# v1.net
KiCad netlist of a schematic drawn in EAGLE
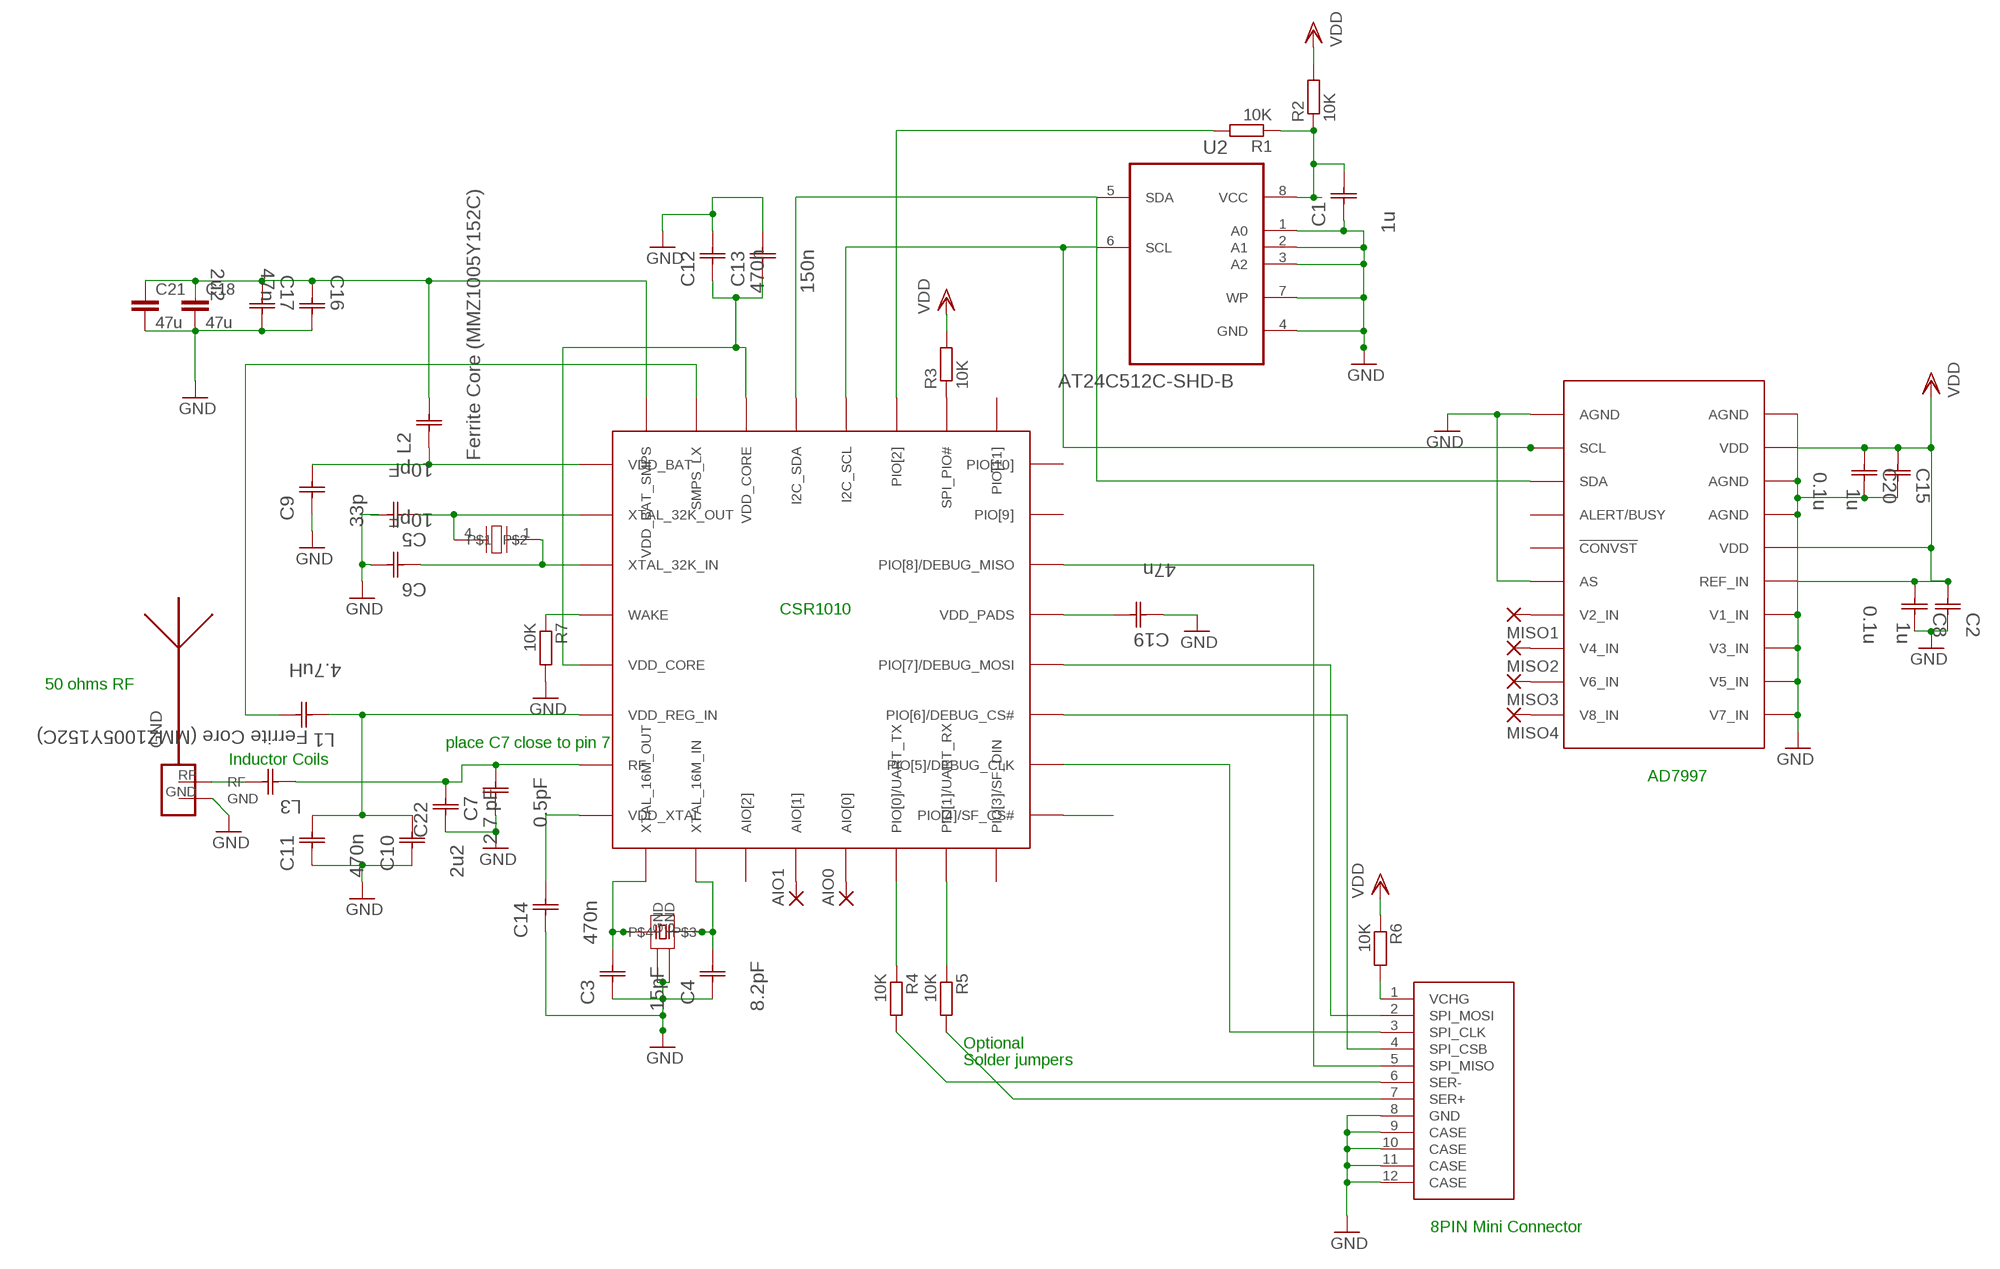
[diagram p0: schematic, sheet 1]

(export (version "E")
  (design (tool "Eeschema 10.0.6"))
  (components
    (comp (ref "AIO0")
      (value "1,6/0,8")
      (footprint "eagle-import:1,6_0,8")
      (libsource (lib "eagle-import") (part "1,6/0,8"))
    )
    (comp (ref "AIO1")
      (value "1,6/0,8")
      (footprint "eagle-import:1,6_0,8")
      (libsource (lib "eagle-import") (part "1,6/0,8"))
    )
    (comp (ref "C1")
      (value "1u")
      (footprint "eagle-import:CAPC1005X60N")
      (fields (field (name "MPN") "UQCL2A100JAT2A/500") (field (name "TOLERANCE") "±5%"))
      (libsource (lib "eagle-import") (part "UQCL2A100JAT2A/500"))
    )
    (comp (ref "C2")
      (value "1u")
      (footprint "eagle-import:CAPC1005X60N")
      (fields (field (name "MPN") "UQCL2A100JAT2A/500") (field (name "TOLERANCE") "±5%"))
      (libsource (lib "eagle-import") (part "UQCL2A100JAT2A/500"))
    )
    (comp (ref "C3")
      (value "15pF")
      (footprint "eagle-import:CAPC1005X60N")
      (fields (field (name "MPN") "UQCL2A150JAT2A/500") (field (name "TOLERANCE") "±5%"))
      (libsource (lib "eagle-import") (part "UQCL2A150JAT2A/500"))
    )
    (comp (ref "C4")
      (value "8.2pF")
      (footprint "eagle-import:CAPC1005X60N")
      (fields (field (name "MPN") "UQCL2A8R2CAT2A/500") (field (name "TOLERANCE") "±.25 pF"))
      (libsource (lib "eagle-import") (part "UQCL2A8R2CAT2A/500"))
    )
    (comp (ref "C5")
      (value "10pF")
      (footprint "eagle-import:CAPC1005X60N")
      (fields (field (name "MPN") "UQCL2A100JAT2A/500") (field (name "TOLERANCE") "±5%"))
      (libsource (lib "eagle-import") (part "UQCL2A100JAT2A/500"))
    )
    (comp (ref "C6")
      (value "10pF")
      (footprint "eagle-import:CAPC1005X60N")
      (fields (field (name "MPN") "UQCL2A100JAT2A/500") (field (name "TOLERANCE") "±5%"))
      (libsource (lib "eagle-import") (part "UQCL2A100JAT2A/500"))
    )
    (comp (ref "C7")
      (value "0.5pF")
      (footprint "eagle-import:CAPC1005X60N")
      (fields (field (name "MPN") "UQCL2A0R5BAT2A/500") (field (name "TOLERANCE") "±.1 pF"))
      (libsource (lib "eagle-import") (part "UQCL2A0R5BAT2A/500"))
    )
    (comp (ref "C8")
      (value "0.1u")
      (footprint "eagle-import:CAPC1005X60N")
      (fields (field (name "MPN") "UQCL2A100JAT2A/500") (field (name "TOLERANCE") "±5%"))
      (libsource (lib "eagle-import") (part "UQCL2A100JAT2A/500"))
    )
    (comp (ref "C9")
      (value "33p")
      (footprint "eagle-import:CAPC1005X60N")
      (fields (field (name "MPN") "UQCL2A100JAT2A/500") (field (name "TOLERANCE") "±5%"))
      (libsource (lib "eagle-import") (part "UQCL2A100JAT2A/500"))
    )
    (comp (ref "C10")
      (value "2u2")
      (footprint "eagle-import:CAPC1005X60N")
      (fields (field (name "MPN") "UQCL2A100JAT2A/500") (field (name "TOLERANCE") "±5%"))
      (libsource (lib "eagle-import") (part "UQCL2A100JAT2A/500"))
    )
    (comp (ref "C11")
      (value "470n")
      (footprint "eagle-import:CAPC1005X60N")
      (fields (field (name "MPN") "UQCL2A100JAT2A/500") (field (name "TOLERANCE") "±5%"))
      (libsource (lib "eagle-import") (part "UQCL2A100JAT2A/500"))
    )
    (comp (ref "C12")
      (value "470n")
      (footprint "eagle-import:CAPC1005X60N")
      (fields (field (name "MPN") "UQCL2A100JAT2A/500") (field (name "TOLERANCE") "±5%"))
      (libsource (lib "eagle-import") (part "UQCL2A100JAT2A/500"))
    )
    (comp (ref "C13")
      (value "150n")
      (footprint "eagle-import:CAPC1005X60N")
      (fields (field (name "MPN") "UQCL2A100JAT2A/500") (field (name "TOLERANCE") "±5%"))
      (libsource (lib "eagle-import") (part "UQCL2A100JAT2A/500"))
    )
    (comp (ref "C14")
      (value "470n")
      (footprint "eagle-import:CAPC1005X60N")
      (fields (field (name "MPN") "UQCL2A100JAT2A/500") (field (name "TOLERANCE") "±5%"))
      (libsource (lib "eagle-import") (part "UQCL2A100JAT2A/500"))
    )
    (comp (ref "C15")
      (value "1u")
      (footprint "eagle-import:CAPC1005X60N")
      (fields (field (name "MPN") "UQCL2A100JAT2A/500") (field (name "TOLERANCE") "±5%"))
      (libsource (lib "eagle-import") (part "UQCL2A100JAT2A/500"))
    )
    (comp (ref "C16")
      (value "47n")
      (footprint "eagle-import:CAPC1005X60N")
      (fields (field (name "MPN") "UQCL2A1R0BAT2A/500") (field (name "TOLERANCE") "±.1 pF"))
      (libsource (lib "eagle-import") (part "UQCL2A1R0BAT2A/500"))
    )
    (comp (ref "C17")
      (value "2u2")
      (footprint "eagle-import:CAPC1005X60N")
      (fields (field (name "MPN") "UQCL2A1R0BAT2A/500") (field (name "TOLERANCE") "±.1 pF"))
      (libsource (lib "eagle-import") (part "UQCL2A1R0BAT2A/500"))
    )
    (comp (ref "C18")
      (value "47u")
      (footprint "eagle-import:C0805")
      (libsource (lib "eagle-import") (part "C-EUC0805"))
    )
    (comp (ref "C19")
      (value "47n")
      (footprint "eagle-import:CAPC1005X60N")
      (fields (field (name "MPN") "UQCL2A100JAT2A/500") (field (name "TOLERANCE") "±5%"))
      (libsource (lib "eagle-import") (part "UQCL2A100JAT2A/500"))
    )
    (comp (ref "C20")
      (value "0.1u")
      (footprint "eagle-import:CAPC1005X60N")
      (fields (field (name "MPN") "UQCL2A100JAT2A/500") (field (name "TOLERANCE") "±5%"))
      (libsource (lib "eagle-import") (part "UQCL2A100JAT2A/500"))
    )
    (comp (ref "C21")
      (value "47u")
      (footprint "eagle-import:C0805")
      (libsource (lib "eagle-import") (part "C-EUC0805"))
    )
    (comp (ref "C22")
      (value "2.7 pF")
      (footprint "eagle-import:CAPC1005X60N")
      (fields (field (name "MPN") "UQCL2A0R5BAT2A/500") (field (name "TOLERANCE") "±.1 pF"))
      (libsource (lib "eagle-import") (part "UQCL2A0R5BAT2A/500"))
    )
    (comp (ref "GND")
      (value "ANTENNA_1LEFT")
      (footprint "eagle-import:SWRA117D_LEFT")
      (libsource (lib "eagle-import") (part "ANTENNA_1LEFT"))
    )
    (comp (ref "L1")
      (value "4.7uH")
      (footprint "eagle-import:CAPC3225X127N")
      (fields (field (name "MPN") "12107C102JAT2A") (field (name "TOLERANCE") "±5%"))
      (libsource (lib "eagle-import") (part "12107C102JAT2A"))
    )
    (comp (ref "L2")
      (value "Ferrite Core (MMZ1005Y152C)")
      (footprint "eagle-import:CAPC1005X60N")
      (fields (field (name "MPN") "UQCL2A100JAT2A/500") (field (name "TOLERANCE") "±5%"))
      (libsource (lib "eagle-import") (part "UQCL2A100JAT2A/500"))
    )
    (comp (ref "L3")
      (value "Ferrite Core (MMZ1005Y152C)")
      (footprint "eagle-import:CAPC1005X60N")
      (fields (field (name "MPN") "UQCL2A100JAT2A/500") (field (name "TOLERANCE") "±5%"))
      (libsource (lib "eagle-import") (part "UQCL2A100JAT2A/500"))
    )
    (comp (ref "MISO1")
      (value "1,6/0,8")
      (footprint "eagle-import:1,6_0,8")
      (libsource (lib "eagle-import") (part "1,6/0,8"))
    )
    (comp (ref "MISO2")
      (value "1,6/0,8")
      (footprint "eagle-import:1,6_0,8")
      (libsource (lib "eagle-import") (part "1,6/0,8"))
    )
    (comp (ref "MISO3")
      (value "1,6/0,8")
      (footprint "eagle-import:1,6_0,8")
      (libsource (lib "eagle-import") (part "1,6/0,8"))
    )
    (comp (ref "MISO4")
      (value "1,6/0,8")
      (footprint "eagle-import:1,6_0,8")
      (libsource (lib "eagle-import") (part "1,6/0,8"))
    )
    (comp (ref "R1")
      (value "10K")
      (footprint "eagle-import:R0402")
      (libsource (lib "eagle-import") (part "R-EU_R0402"))
    )
    (comp (ref "R2")
      (value "10K")
      (footprint "eagle-import:R0402")
      (libsource (lib "eagle-import") (part "R-EU_R0402"))
    )
    (comp (ref "R3")
      (value "10K")
      (footprint "eagle-import:R0402")
      (libsource (lib "eagle-import") (part "R-EU_R0402"))
    )
    (comp (ref "R4")
      (value "10K")
      (footprint "eagle-import:R0402")
      (libsource (lib "eagle-import") (part "R-EU_R0402"))
    )
    (comp (ref "R5")
      (value "10K")
      (footprint "eagle-import:R0402")
      (libsource (lib "eagle-import") (part "R-EU_R0402"))
    )
    (comp (ref "R6")
      (value "10K")
      (footprint "eagle-import:R0402")
      (libsource (lib "eagle-import") (part "R-EU_R0402"))
    )
    (comp (ref "R7")
      (value "10K")
      (footprint "eagle-import:R0402")
      (libsource (lib "eagle-import") (part "R-EU_R0402"))
    )
    (comp (ref "U$1")
      (value "CSR1010A05-IQQM-R")
      (footprint "eagle-import:CSR1010A05-IQQM-R")
      (libsource (lib "eagle-import") (part "CSR1010A05-IQQM-R"))
    )
    (comp (ref "U$2")
      (value "8PIN_SMT_CONNECTOR")
      (footprint "eagle-import:8PIN_SMT_CONNECTOR")
      (libsource (lib "eagle-import") (part "8PIN_SMT_CONNECTOR"))
    )
    (comp (ref "U$3")
      (value "TSX3225")
      (footprint "eagle-import:TSX3225")
      (libsource (lib "eagle-import") (part "TSX3225"))
    )
    (comp (ref "U$4")
      (value "SSP-T7-F")
      (footprint "eagle-import:SSP-T7-F")
      (libsource (lib "eagle-import") (part "SSP-T7-F"))
    )
    (comp (ref "U$5")
      (value "AD7997")
      (footprint "eagle-import:AD7997")
      (libsource (lib "eagle-import") (part "AD7997"))
    )
    (comp (ref "U2")
      (value "AT24C512C-SHD-B")
      (footprint "eagle-import:SOIC127P798X216-8N")
      (libsource (lib "eagle-import") (part "AT24C512C-SHD-B"))
    )
  )
  (nets
    (net (code "1") (name "GND") (class "Default")
      (node (ref "C1") (pin "2") (pinfunction "C1_2") (pintype "passive"))
      (node (ref "C10") (pin "2") (pinfunction "C1_2") (pintype "passive"))
      (node (ref "C11") (pin "2") (pinfunction "C1_2") (pintype "passive"))
      (node (ref "C12") (pin "1") (pinfunction "C2_1") (pintype "passive"))
      (node (ref "C13") (pin "1") (pinfunction "C2_1") (pintype "passive"))
      (node (ref "C14") (pin "2") (pinfunction "C1_2") (pintype "passive"))
      (node (ref "C15") (pin "2") (pinfunction "C1_2") (pintype "passive"))
      (node (ref "C16") (pin "1") (pinfunction "C2_1") (pintype "passive"))
      (node (ref "C17") (pin "1") (pinfunction "C2_1") (pintype "passive"))
      (node (ref "C18") (pin "2") (pinfunction "2_2") (pintype "passive"))
      (node (ref "C19") (pin "2") (pinfunction "C1_2") (pintype "passive"))
      (node (ref "C2") (pin "2") (pinfunction "C1_2") (pintype "passive"))
      (node (ref "C20") (pin "2") (pinfunction "C1_2") (pintype "passive"))
      (node (ref "C21") (pin "2") (pinfunction "2_2") (pintype "passive"))
      (node (ref "C22") (pin "2") (pinfunction "C1_2") (pintype "passive"))
      (node (ref "C3") (pin "2") (pinfunction "C1_2") (pintype "passive"))
      (node (ref "C4") (pin "2") (pinfunction "C1_2") (pintype "passive"))
      (node (ref "C6") (pin "1") (pinfunction "C2_1") (pintype "passive"))
      (node (ref "C7") (pin "2") (pinfunction "C1_2") (pintype "passive"))
      (node (ref "C8") (pin "2") (pinfunction "C1_2") (pintype "passive"))
      (node (ref "C9") (pin "2") (pinfunction "C1_2") (pintype "passive"))
      (node (ref "R7") (pin "2") (pinfunction "2_2") (pintype "passive"))
      (node (ref "U$2") (pin "10") (pinfunction "CASE_10") (pintype "bidirectional"))
      (node (ref "U$2") (pin "11") (pinfunction "CASE_11") (pintype "bidirectional"))
      (node (ref "U$2") (pin "12") (pinfunction "CASE_12") (pintype "bidirectional"))
      (node (ref "U$2") (pin "8") (pinfunction "GND_8") (pintype "bidirectional"))
      (node (ref "U$2") (pin "9") (pinfunction "CASE_9") (pintype "bidirectional"))
      (node (ref "U$3") (pin "2") (pinfunction "GND_2") (pintype "bidirectional"))
      (node (ref "U$3") (pin "4") (pinfunction "GND_4") (pintype "bidirectional"))
      (node (ref "U$5") (pin "P$01") (pinfunction "AGND_P$01") (pintype "bidirectional"))
      (node (ref "U$5") (pin "P$010") (pinfunction "V7_IN_P$010") (pintype "bidirectional"))
      (node (ref "U$5") (pin "P$015") (pinfunction "AS_P$015") (pintype "bidirectional"))
      (node (ref "U$5") (pin "P$020") (pinfunction "AGND_P$020") (pintype "bidirectional"))
      (node (ref "U$5") (pin "P$03") (pinfunction "AGND_P$03") (pintype "bidirectional"))
      (node (ref "U$5") (pin "P$04") (pinfunction "AGND_P$04") (pintype "bidirectional"))
      (node (ref "U$5") (pin "P$07") (pinfunction "V1_IN_P$07") (pintype "bidirectional"))
      (node (ref "U$5") (pin "P$08") (pinfunction "V3_IN_P$08") (pintype "bidirectional"))
      (node (ref "U$5") (pin "P$09") (pinfunction "V5_IN_P$09") (pintype "bidirectional"))
      (node (ref "U2") (pin "1") (pinfunction "A0_1") (pintype "input"))
      (node (ref "U2") (pin "2") (pinfunction "A1_2") (pintype "input"))
      (node (ref "U2") (pin "3") (pinfunction "A2_3") (pintype "input"))
      (node (ref "U2") (pin "4") (pinfunction "GND_4") (pintype "power_in"))
      (node (ref "U2") (pin "7") (pinfunction "WP_7") (pintype "input"))
    )
    (net (code "2") (name "Net-(AIO0-P)") (class "Default")
      (node (ref "AIO0") (pin "1") (pinfunction "P_1") (pintype "passive"))
      (node (ref "U$1") (pin "AIO[0]") (pinfunction "AIO[0]_AIO[0]") (pintype "output"))
    )
    (net (code "3") (name "Net-(AIO1-P)") (class "Default")
      (node (ref "AIO1") (pin "1") (pinfunction "P_1") (pintype "passive"))
      (node (ref "U$1") (pin "AIO[1]") (pinfunction "AIO[1]_AIO[1]") (pintype "output"))
    )
    (net (code "4") (name "Net-(C1-C2)") (class "Default")
      (node (ref "C1") (pin "1") (pinfunction "C2_1") (pintype "passive"))
      (node (ref "R1") (pin "1") (pinfunction "1_1") (pintype "passive"))
      (node (ref "R2") (pin "1") (pinfunction "1_1") (pintype "passive"))
      (node (ref "U2") (pin "8") (pinfunction "VCC_8") (pintype "power_in"))
    )
    (net (code "5") (name "Net-(C3-C2)") (class "Default")
      (node (ref "C3") (pin "1") (pinfunction "C2_1") (pintype "passive"))
      (node (ref "U$1") (pin "XTAL_16M_OUT") (pinfunction "XTAL_16M_OUT_XTAL_16M_OUT") (pintype "output"))
      (node (ref "U$3") (pin "1") (pinfunction "P$3_1") (pintype "bidirectional"))
    )
    (net (code "6") (name "Net-(C4-C2)") (class "Default")
      (node (ref "C4") (pin "1") (pinfunction "C2_1") (pintype "passive"))
      (node (ref "U$1") (pin "XTAL_16M_IN") (pinfunction "XTAL_16M_IN_XTAL_16M_IN") (pintype "output"))
      (node (ref "U$3") (pin "3") (pinfunction "P$4_3") (pintype "bidirectional"))
    )
    (net (code "7") (name "Net-(C5-C1)") (class "Default")
      (node (ref "C5") (pin "2") (pinfunction "C1_2") (pintype "passive"))
      (node (ref "U$1") (pin "XTAL_32K_OUT") (pinfunction "XTAL_32K_OUT_XTAL_32K_OUT") (pintype "output"))
      (node (ref "U$4") (pin "4") (pinfunction "P$2_4") (pintype "bidirectional"))
    )
    (net (code "8") (name "Net-(C6-C1)") (class "Default")
      (node (ref "C6") (pin "2") (pinfunction "C1_2") (pintype "passive"))
      (node (ref "U$1") (pin "XTAL_32K_IN") (pinfunction "XTAL_32K_IN_XTAL_32K_IN") (pintype "output"))
      (node (ref "U$4") (pin "1") (pinfunction "P$1_1") (pintype "bidirectional"))
    )
    (net (code "9") (name "Net-(C9-C2)") (class "Default")
      (node (ref "C9") (pin "1") (pinfunction "C2_1") (pintype "passive"))
      (node (ref "L2") (pin "2") (pinfunction "C1_2") (pintype "passive"))
      (node (ref "U$1") (pin "VDD_BAT") (pinfunction "VDD_BAT_VDD_BAT") (pintype "output"))
    )
    (net (code "10") (name "Net-(C10-C2)") (class "Default")
      (node (ref "C10") (pin "1") (pinfunction "C2_1") (pintype "passive"))
      (node (ref "C11") (pin "1") (pinfunction "C2_1") (pintype "passive"))
      (node (ref "L1") (pin "1") (pinfunction "C1_1") (pintype "passive"))
      (node (ref "U$1") (pin "VDD_REG_IN") (pinfunction "VDD_REG_IN_VDD_REG_IN") (pintype "output"))
    )
    (net (code "11") (name "Net-(C12-C1)") (class "Default")
      (node (ref "C12") (pin "2") (pinfunction "C1_2") (pintype "passive"))
      (node (ref "C13") (pin "2") (pinfunction "C1_2") (pintype "passive"))
      (node (ref "U$1") (pin "VDD_CORE") (pinfunction "VDD_CORE_VDD_CORE") (pintype "output"))
      (node (ref "U$1") (pin "VDD_CORE@1") (pinfunction "VDD_CORE_VDD_CORE@1") (pintype "bidirectional"))
    )
    (net (code "12") (name "Net-(C14-C2)") (class "Default")
      (node (ref "C14") (pin "1") (pinfunction "C2_1") (pintype "passive"))
      (node (ref "U$1") (pin "VDD_XTAL") (pinfunction "VDD_XTAL_VDD_XTAL") (pintype "output"))
    )
    (net (code "13") (name "Net-(C16-C1)") (class "Default")
      (node (ref "C16") (pin "2") (pinfunction "C1_2") (pintype "passive"))
      (node (ref "C17") (pin "2") (pinfunction "C1_2") (pintype "passive"))
      (node (ref "C18") (pin "1") (pinfunction "1_1") (pintype "passive"))
      (node (ref "C21") (pin "1") (pinfunction "1_1") (pintype "passive"))
      (node (ref "L2") (pin "1") (pinfunction "C2_1") (pintype "passive"))
      (node (ref "U$1") (pin "VDD_BAT_SMPS") (pinfunction "VDD_BAT_SMPS_VDD_BAT_SMPS") (pintype "output"))
    )
    (net (code "14") (name "Net-(C19-C2)") (class "Default")
      (node (ref "C19") (pin "1") (pinfunction "C2_1") (pintype "passive"))
      (node (ref "U$1") (pin "VDD_PADS") (pinfunction "VDD_PADS_VDD_PADS") (pintype "output"))
    )
    (net (code "15") (name "Net-(C22-C2)") (class "Default")
      (node (ref "C22") (pin "1") (pinfunction "C2_1") (pintype "passive"))
      (node (ref "C7") (pin "1") (pinfunction "C2_1") (pintype "passive"))
      (node (ref "L3") (pin "2") (pinfunction "C1_2") (pintype "passive"))
      (node (ref "U$1") (pin "RF") (pinfunction "RF_RF") (pintype "output"))
    )
    (net (code "16") (name "Net-(L1-C2)") (class "Default")
      (node (ref "L1") (pin "2") (pinfunction "C2_2") (pintype "passive"))
      (node (ref "U$1") (pin "SMPS_LX") (pinfunction "SMPS_LX_SMPS_LX") (pintype "output"))
    )
    (net (code "17") (name "Net-(MISO1-P)") (class "Default")
      (node (ref "MISO1") (pin "1") (pinfunction "P_1") (pintype "passive"))
      (node (ref "U$5") (pin "P$014") (pinfunction "V2_IN_P$014") (pintype "bidirectional"))
    )
    (net (code "18") (name "Net-(MISO2-P)") (class "Default")
      (node (ref "MISO2") (pin "1") (pinfunction "P_1") (pintype "passive"))
      (node (ref "U$5") (pin "P$013") (pinfunction "V4_IN_P$013") (pintype "bidirectional"))
    )
    (net (code "19") (name "Net-(MISO3-P)") (class "Default")
      (node (ref "MISO3") (pin "1") (pinfunction "P_1") (pintype "passive"))
      (node (ref "U$5") (pin "P$012") (pinfunction "V6_IN_P$012") (pintype "bidirectional"))
    )
    (net (code "20") (name "Net-(MISO4-P)") (class "Default")
      (node (ref "MISO4") (pin "1") (pinfunction "P_1") (pintype "passive"))
      (node (ref "U$5") (pin "P$011") (pinfunction "V8_IN_P$011") (pintype "bidirectional"))
    )
    (net (code "21") (name "Net-(R1-Pad2)") (class "Default")
      (node (ref "R1") (pin "2") (pinfunction "2_2") (pintype "passive"))
      (node (ref "U$1") (pin "PIO[2]") (pinfunction "PIO[2]_PIO[2]") (pintype "output"))
    )
    (net (code "22") (name "Net-(R3-Pad1)") (class "Default")
      (node (ref "R3") (pin "1") (pinfunction "1_1") (pintype "passive"))
      (node (ref "U$1") (pin "SPI_PIO#") (pinfunction "SPI_PIO#_SPI_PIO#") (pintype "output"))
    )
    (net (code "23") (name "Net-(R4-Pad1)") (class "Default")
      (node (ref "R4") (pin "1") (pinfunction "1_1") (pintype "passive"))
      (node (ref "U$1") (pin "PIO[0]/UART_TX") (pinfunction "PIO[0]/UART_TX_PIO[0]/UART_TX") (pintype "output"))
    )
    (net (code "24") (name "Net-(R5-Pad1)") (class "Default")
      (node (ref "R5") (pin "1") (pinfunction "1_1") (pintype "passive"))
      (node (ref "U$1") (pin "PIO[1]/UART_RX") (pinfunction "PIO[1]/UART_RX_PIO[1]/UART_RX") (pintype "output"))
    )
    (net (code "25") (name "Net-(R7-Pad1)") (class "Default")
      (node (ref "R7") (pin "1") (pinfunction "1_1") (pintype "passive"))
      (node (ref "U$1") (pin "WAKE") (pinfunction "WAKE_WAKE") (pintype "output"))
    )
    (net (code "26") (name "Net-(U$2-SER+)") (class "Default")
      (node (ref "R5") (pin "2") (pinfunction "2_2") (pintype "passive"))
      (node (ref "U$2") (pin "7") (pinfunction "SER+_7") (pintype "bidirectional"))
    )
    (net (code "27") (name "Net-(U$2-SER-)") (class "Default")
      (node (ref "R4") (pin "2") (pinfunction "2_2") (pintype "passive"))
      (node (ref "U$2") (pin "6") (pinfunction "SER-_6") (pintype "bidirectional"))
    )
    (net (code "28") (name "Net-(U$2-SPI_CLK)") (class "Default")
      (node (ref "U$1") (pin "PIO[5]/DEBUG_CLK") (pinfunction "PIO[5]/DEBUG_CLK_PIO[5]/DEBUG_CLK") (pintype "output"))
      (node (ref "U$2") (pin "3") (pinfunction "SPI_CLK_3") (pintype "bidirectional"))
    )
    (net (code "29") (name "Net-(U$2-SPI_CSB)") (class "Default")
      (node (ref "U$1") (pin "PIO[6]/DEBUG_CS#") (pinfunction "PIO[6]/DEBUG_CS#_PIO[6]/DEBUG_CS#") (pintype "output"))
      (node (ref "U$2") (pin "4") (pinfunction "SPI_CSB_4") (pintype "bidirectional"))
    )
    (net (code "30") (name "Net-(U$2-SPI_MISO)") (class "Default")
      (node (ref "U$1") (pin "PIO[8]/DEBUG_MISO") (pinfunction "PIO[8]/DEBUG_MISO_PIO[8]/DEBUG_MISO") (pintype "output"))
      (node (ref "U$2") (pin "5") (pinfunction "SPI_MISO_5") (pintype "bidirectional"))
    )
    (net (code "31") (name "Net-(U$2-SPI_MOSI)") (class "Default")
      (node (ref "U$1") (pin "PIO[7]/DEBUG_MOSI") (pinfunction "PIO[7]/DEBUG_MOSI_PIO[7]/DEBUG_MOSI") (pintype "output"))
      (node (ref "U$2") (pin "2") (pinfunction "SPI_MOSI_2") (pintype "bidirectional"))
    )
    (net (code "32") (name "Net-(U$2-VCHG)") (class "Default")
      (node (ref "R6") (pin "2") (pinfunction "2_2") (pintype "passive"))
      (node (ref "U$2") (pin "1") (pinfunction "VCHG_1") (pintype "bidirectional"))
    )
    (net (code "33") (name "Net-(U$5-SCL)") (class "Default")
      (node (ref "U$1") (pin "I2C_SCL") (pinfunction "I2C_SCL_I2C_SCL") (pintype "output"))
      (node (ref "U$5") (pin "P$019") (pinfunction "SCL_P$019") (pintype "bidirectional"))
      (node (ref "U2") (pin "6") (pinfunction "SCL_6") (pintype "input"))
    )
    (net (code "34") (name "Net-(U$5-SDA)") (class "Default")
      (node (ref "U$1") (pin "I2C_SDA") (pinfunction "I2C_SDA_I2C_SDA") (pintype "output"))
      (node (ref "U$5") (pin "P$018") (pinfunction "SDA_P$018") (pintype "bidirectional"))
      (node (ref "U2") (pin "5") (pinfunction "SDA_5") (pintype "bidirectional"))
    )
    (net (code "35") (name "VDD") (class "Default")
      (node (ref "C15") (pin "1") (pinfunction "C2_1") (pintype "passive"))
      (node (ref "C2") (pin "1") (pinfunction "C2_1") (pintype "passive"))
      (node (ref "C20") (pin "1") (pinfunction "C2_1") (pintype "passive"))
      (node (ref "C8") (pin "1") (pinfunction "C2_1") (pintype "passive"))
      (node (ref "R2") (pin "2") (pinfunction "2_2") (pintype "passive"))
      (node (ref "R3") (pin "2") (pinfunction "2_2") (pintype "passive"))
      (node (ref "R6") (pin "1") (pinfunction "1_1") (pintype "passive"))
      (node (ref "U$5") (pin "P$02") (pinfunction "VDD_P$02") (pintype "bidirectional"))
      (node (ref "U$5") (pin "P$05") (pinfunction "VDD_P$05") (pintype "bidirectional"))
      (node (ref "U$5") (pin "P$06") (pinfunction "REF_IN_P$06") (pintype "bidirectional"))
    )
    (net (code "36") (name "unconnected-(C5-C2-Pad1)") (class "Default")
      (node (ref "C5") (pin "1") (pinfunction "C2_1") (pintype "passive"))
    )
    (net (code "37") (name "unconnected-(GND-PadGND)") (class "Default")
      (node (ref "GND") (pin "GND") (pinfunction "GND_GND") (pintype "passive"))
    )
    (net (code "38") (name "unconnected-(GND-PadRF)") (class "Default")
      (node (ref "GND") (pin "RF") (pinfunction "RF_RF") (pintype "bidirectional"))
    )
    (net (code "39") (name "unconnected-(L3-C2-Pad1)") (class "Default")
      (node (ref "L3") (pin "1") (pinfunction "C2_1") (pintype "passive"))
    )
    (net (code "40") (name "unconnected-(U$1-PadAIO[2])") (class "Default")
      (node (ref "U$1") (pin "AIO[2]") (pinfunction "AIO[2]_AIO[2]") (pintype "output"))
    )
    (net (code "41") (name "unconnected-(U$1-PadPIO[3]{slash}SF_DIN)") (class "Default")
      (node (ref "U$1") (pin "PIO[3]/SF_DIN") (pinfunction "PIO[3]/SF_DIN_PIO[3]/SF_DIN") (pintype "output"))
    )
    (net (code "42") (name "unconnected-(U$1-PadPIO[4]{slash}SF_CS#)") (class "Default")
      (node (ref "U$1") (pin "PIO[4]/SF_CS#") (pinfunction "PIO[4]/SF_CS#_PIO[4]/SF_CS#") (pintype "output"))
    )
    (net (code "43") (name "unconnected-(U$1-PadPIO[9])") (class "Default")
      (node (ref "U$1") (pin "PIO[9]") (pinfunction "PIO[9]_PIO[9]") (pintype "output"))
    )
    (net (code "44") (name "unconnected-(U$1-PadPIO[10])") (class "Default")
      (node (ref "U$1") (pin "PIO[10]") (pinfunction "PIO[10]_PIO[10]") (pintype "output"))
    )
    (net (code "45") (name "unconnected-(U$1-PadPIO[11])") (class "Default")
      (node (ref "U$1") (pin "PIO[11]") (pinfunction "PIO[11]_PIO[11]") (pintype "output"))
    )
    (net (code "46") (name "unconnected-(U$5-ALERT{slash}BUSY-PadP$017)") (class "Default")
      (node (ref "U$5") (pin "P$017") (pinfunction "ALERT/BUSY_P$017") (pintype "bidirectional"))
    )
    (net (code "47") (name "unconnected-(U$5-~{CONVST}-PadP$016)") (class "Default")
      (node (ref "U$5") (pin "P$016") (pinfunction "~{CONVST}_P$016") (pintype "bidirectional"))
    )
  )
)
